# DDS-Gen.net
KiCad netlist of a schematic drawn in EAGLE
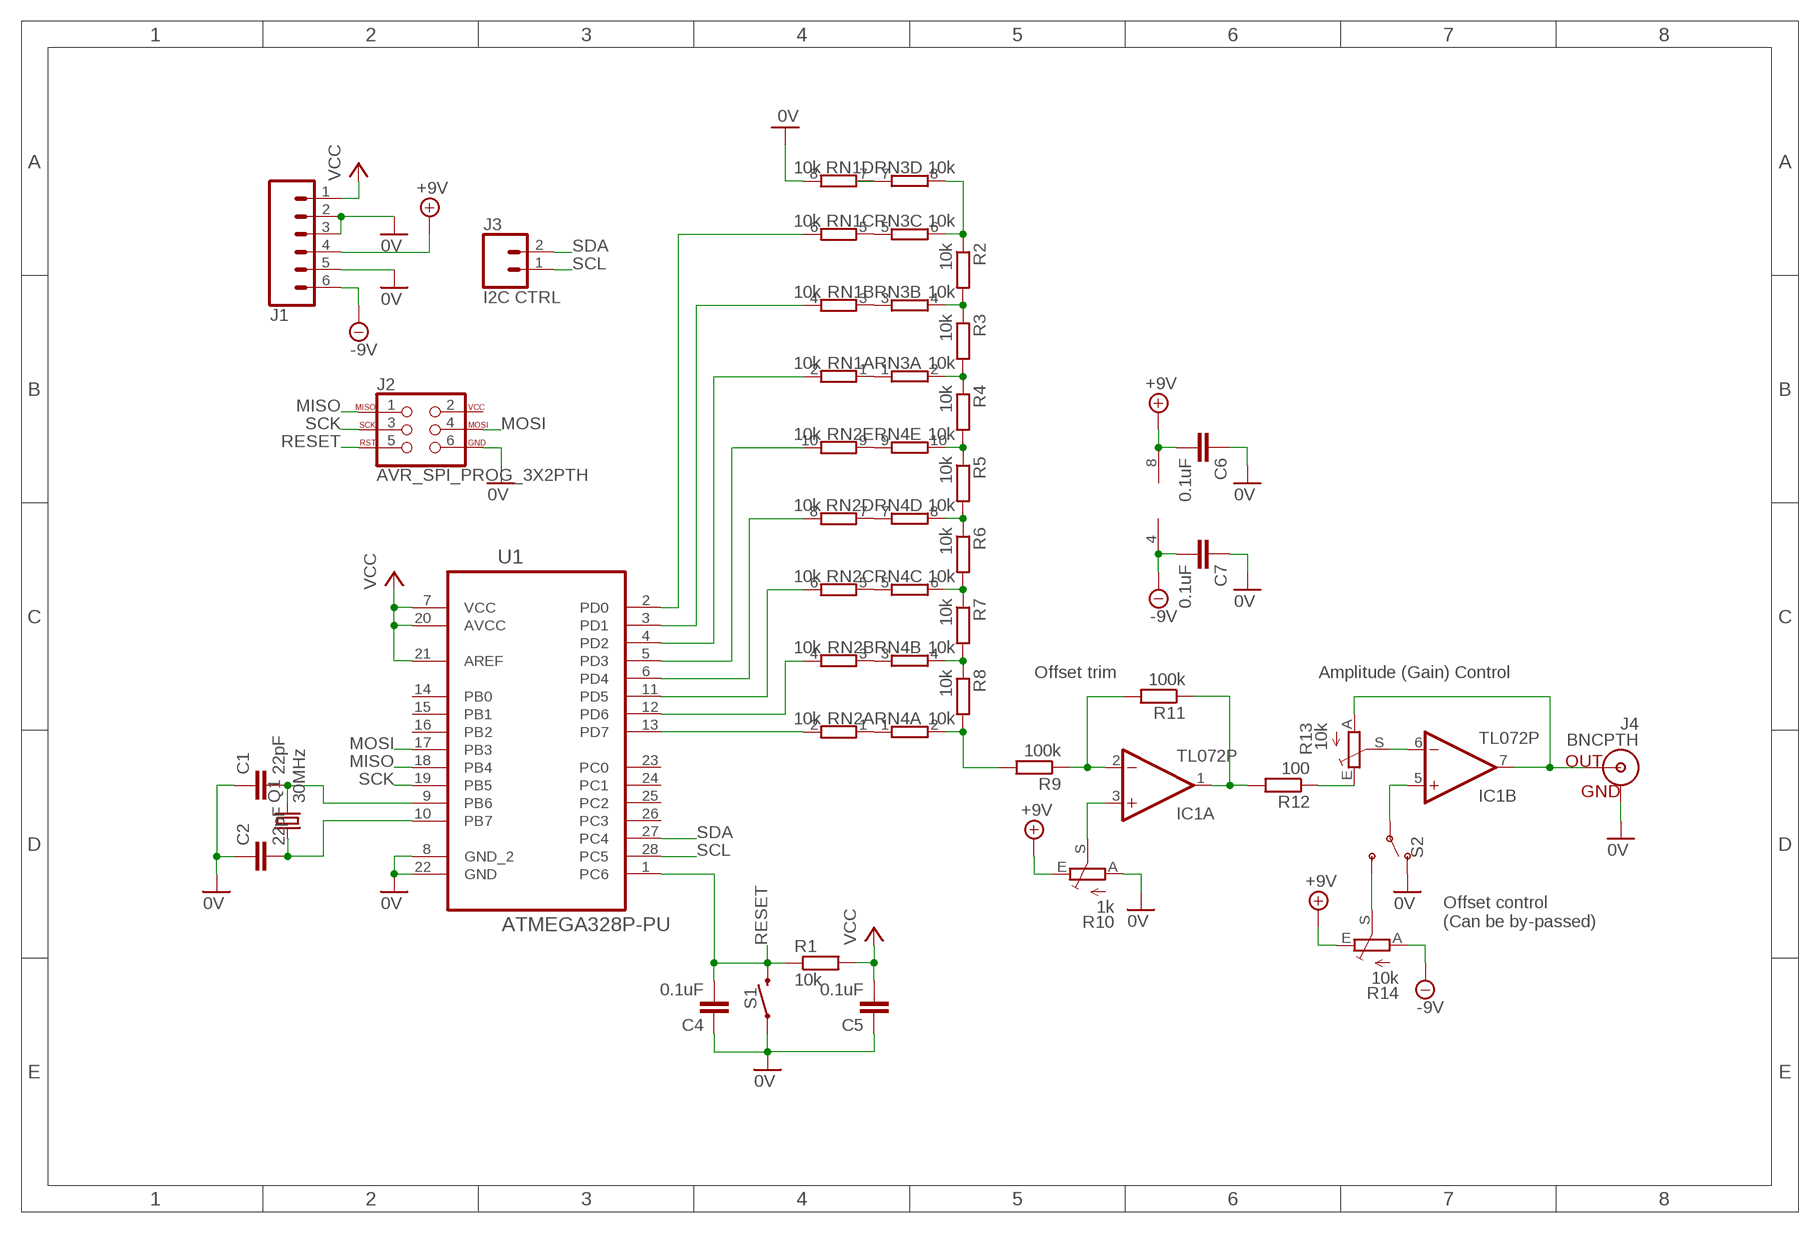
[diagram p0: schematic, sheet 1]

(export (version "E")
  (design (tool "Eeschema 10.0.6"))
  (components
    (comp (ref "C1")
      (value "22pF")
      (footprint "eagle-import:C025-025X050")
      (libsource (lib "eagle-import") (part "C-EU025-025X050"))
    )
    (comp (ref "C2")
      (value "22pF")
      (footprint "eagle-import:C025-025X050")
      (libsource (lib "eagle-import") (part "C-EU025-025X050"))
    )
    (comp (ref "C4")
      (value "0.1uF")
      (footprint "eagle-import:C025-025X050")
      (libsource (lib "eagle-import") (part "C-EU025-025X050"))
    )
    (comp (ref "C5")
      (value "0.1uF")
      (footprint "eagle-import:C025-025X050")
      (libsource (lib "eagle-import") (part "C-EU025-025X050"))
    )
    (comp (ref "C6")
      (value "0.1uF")
      (footprint "eagle-import:C025-025X050")
      (libsource (lib "eagle-import") (part "C-EU025-025X050"))
    )
    (comp (ref "C7")
      (value "0.1uF")
      (footprint "eagle-import:C025-025X050")
      (libsource (lib "eagle-import") (part "C-EU025-025X050"))
    )
    (comp (ref "IC1")
      (value "TL072P")
      (footprint "eagle-import:DIL08")
      (libsource (lib "eagle-import") (part "TL072P"))
    )
    (comp (ref "J1")
      (value "CONN_06POLAR")
      (footprint "eagle-import:MOLEX-1X6")
      (libsource (lib "eagle-import") (part "CONN_06POLAR"))
    )
    (comp (ref "J2")
      (value "AVR_SPI_PROG_3X2PTH")
      (footprint "eagle-import:2X3")
      (libsource (lib "eagle-import") (part "AVR_SPI_PROG_3X2PTH"))
    )
    (comp (ref "J3")
      (value "I2C CTRL")
      (footprint "eagle-import:MOLEX-1X2")
      (libsource (lib "eagle-import") (part "CONN_02POLAR"))
    )
    (comp (ref "J4")
      (value "BNCPTH")
      (footprint "eagle-import:BNC")
      (libsource (lib "eagle-import") (part "BNCPTH"))
    )
    (comp (ref "Q1")
      (value "30MHz")
      (footprint "eagle-import:HC49_S")
      (libsource (lib "eagle-import") (part "CRYSTALHC49S"))
    )
    (comp (ref "R1")
      (value "10k")
      (footprint "eagle-import:0204_5")
      (libsource (lib "eagle-import") (part "R-EU_0204/5"))
    )
    (comp (ref "R2")
      (value "10k")
      (footprint "eagle-import:0204_5")
      (libsource (lib "eagle-import") (part "R-EU_0204/5"))
    )
    (comp (ref "R3")
      (value "10k")
      (footprint "eagle-import:0204_5")
      (libsource (lib "eagle-import") (part "R-EU_0204/5"))
    )
    (comp (ref "R4")
      (value "10k")
      (footprint "eagle-import:0204_5")
      (libsource (lib "eagle-import") (part "R-EU_0204/5"))
    )
    (comp (ref "R5")
      (value "10k")
      (footprint "eagle-import:0204_5")
      (libsource (lib "eagle-import") (part "R-EU_0204/5"))
    )
    (comp (ref "R6")
      (value "10k")
      (footprint "eagle-import:0204_5")
      (libsource (lib "eagle-import") (part "R-EU_0204/5"))
    )
    (comp (ref "R7")
      (value "10k")
      (footprint "eagle-import:0204_5")
      (libsource (lib "eagle-import") (part "R-EU_0204/5"))
    )
    (comp (ref "R8")
      (value "10k")
      (footprint "eagle-import:0204_5")
      (libsource (lib "eagle-import") (part "R-EU_0204/5"))
    )
    (comp (ref "R9")
      (value "100k")
      (footprint "eagle-import:0204_5")
      (libsource (lib "eagle-import") (part "R-EU_0204/5"))
    )
    (comp (ref "R10")
      (value "1k")
      (footprint "eagle-import:S64W")
      (libsource (lib "eagle-import") (part "TRIM_EU-S64W"))
    )
    (comp (ref "R11")
      (value "100k")
      (footprint "eagle-import:0204V")
      (libsource (lib "eagle-import") (part "R-EU_0204/2V"))
    )
    (comp (ref "R12")
      (value "100")
      (footprint "eagle-import:0207_12")
      (libsource (lib "eagle-import") (part "R-EU_0207/12"))
    )
    (comp (ref "R13")
      (value "10k")
      (footprint "eagle-import:CIP20C-6MM")
      (libsource (lib "eagle-import") (part "TRIM_EU-CIP20C-6MM"))
    )
    (comp (ref "R14")
      (value "10k")
      (footprint "eagle-import:CIP20C-6MM")
      (libsource (lib "eagle-import") (part "TRIM_EU-CIP20C-6MM"))
    )
    (comp (ref "RN1")
      (value "10k")
      (footprint "eagle-import:SIL10")
      (libsource (lib "eagle-import") (part "E5R"))
    )
    (comp (ref "RN2")
      (value "10k")
      (footprint "eagle-import:SIL10")
      (libsource (lib "eagle-import") (part "E5R"))
    )
    (comp (ref "RN3")
      (value "10k")
      (footprint "eagle-import:SIL10")
      (libsource (lib "eagle-import") (part "E5R"))
    )
    (comp (ref "RN4")
      (value "10k")
      (footprint "eagle-import:SIL10")
      (libsource (lib "eagle-import") (part "E5R"))
    )
    (comp (ref "S1")
      (value "MOMENTARY-SWITCH-SPST-PTH-6.0MM")
      (footprint "eagle-import:TACTILE_SWITCH_PTH_6.0MM")
      (libsource (lib "eagle-import") (part "MOMENTARY-SWITCH-SPST-PTH-6.0MM"))
    )
    (comp (ref "S2")
      (value "SWITCH-SPDT-PTH-11.6X4.0MM")
      (footprint "eagle-import:SWITCH_SPDT_PTH_11.6X4.0MM")
      (libsource (lib "eagle-import") (part "SWITCH-SPDT-PTH-11.6X4.0MM"))
    )
    (comp (ref "U1")
      (value "ATMEGA328P-PU")
      (footprint "eagle-import:DIP254P762X457-28")
      (libsource (lib "eagle-import") (part "ATMEGA328P-PU"))
    )
  )
  (nets
    (net (code "1") (name "+9V") (class "Default")
      (node (ref "C6") (pin "2") (pinfunction "2_2") (pintype "passive"))
      (node (ref "IC1") (pin "8") (pinfunction "V+_8") (pintype "power_in"))
      (node (ref "J1") (pin "4") (pinfunction "4_4") (pintype "passive"))
      (node (ref "R10") (pin "E") (pinfunction "E_E") (pintype "passive"))
      (node (ref "R14") (pin "E") (pinfunction "E_E") (pintype "passive"))
    )
    (net (code "2") (name "-9V") (class "Default")
      (node (ref "C7") (pin "2") (pinfunction "2_2") (pintype "passive"))
      (node (ref "IC1") (pin "4") (pinfunction "V-_4") (pintype "power_in"))
      (node (ref "J1") (pin "6") (pinfunction "6_6") (pintype "passive"))
      (node (ref "R14") (pin "A") (pinfunction "A_A") (pintype "passive"))
    )
    (net (code "3") (name "/MISO") (class "Default")
      (node (ref "J2") (pin "1") (pinfunction "1_1") (pintype "passive"))
      (node (ref "U1") (pin "18") (pinfunction "PB4_18") (pintype "bidirectional"))
    )
    (net (code "4") (name "/MOSI") (class "Default")
      (node (ref "J2") (pin "4") (pinfunction "4_4") (pintype "passive"))
      (node (ref "U1") (pin "17") (pinfunction "PB3_17") (pintype "bidirectional"))
    )
    (net (code "5") (name "/RESET") (class "Default")
      (node (ref "C4") (pin "2") (pinfunction "2_2") (pintype "passive"))
      (node (ref "J2") (pin "5") (pinfunction "5_5") (pintype "passive"))
      (node (ref "R1") (pin "1") (pinfunction "1_1") (pintype "passive"))
      (node (ref "S1") (pin "3") (pinfunction "2_3") (pintype "passive"))
      (node (ref "U1") (pin "1") (pinfunction "PC6_1") (pintype "bidirectional"))
    )
    (net (code "6") (name "/SCK") (class "Default")
      (node (ref "J2") (pin "3") (pinfunction "3_3") (pintype "passive"))
      (node (ref "U1") (pin "19") (pinfunction "PB5_19") (pintype "bidirectional"))
    )
    (net (code "7") (name "/SCL") (class "Default")
      (node (ref "J3") (pin "1") (pinfunction "1_1") (pintype "passive"))
      (node (ref "U1") (pin "28") (pinfunction "PC5_28") (pintype "bidirectional"))
    )
    (net (code "8") (name "/SDA") (class "Default")
      (node (ref "J3") (pin "2") (pinfunction "2_2") (pintype "passive"))
      (node (ref "U1") (pin "27") (pinfunction "PC4_27") (pintype "bidirectional"))
    )
    (net (code "9") (name "0V") (class "Default")
      (node (ref "C1") (pin "1") (pinfunction "1_1") (pintype "passive"))
      (node (ref "C2") (pin "1") (pinfunction "1_1") (pintype "passive"))
      (node (ref "C4") (pin "1") (pinfunction "1_1") (pintype "passive"))
      (node (ref "C5") (pin "1") (pinfunction "1_1") (pintype "passive"))
      (node (ref "C6") (pin "1") (pinfunction "1_1") (pintype "passive"))
      (node (ref "C7") (pin "1") (pinfunction "1_1") (pintype "passive"))
      (node (ref "J1") (pin "2") (pinfunction "2_2") (pintype "passive"))
      (node (ref "J1") (pin "3") (pinfunction "3_3") (pintype "passive"))
      (node (ref "J1") (pin "5") (pinfunction "5_5") (pintype "passive"))
      (node (ref "J2") (pin "6") (pinfunction "6_6") (pintype "passive"))
      (node (ref "J4") (pin "GND") (pinfunction "GND_GND") (pintype "bidirectional"))
      (node (ref "R10") (pin "A") (pinfunction "A_A") (pintype "passive"))
      (node (ref "RN1") (pin "8") (pinfunction "2_8") (pintype "passive"))
      (node (ref "S1") (pin "1") (pinfunction "1_1") (pintype "passive"))
      (node (ref "S2") (pin "1") (pinfunction "O_1") (pintype "passive"))
      (node (ref "U1") (pin "22") (pinfunction "GND_22") (pintype "passive"))
      (node (ref "U1") (pin "8") (pinfunction "GND_2_8") (pintype "passive"))
    )
    (net (code "10") (name "Net-(IC1A-+IN)") (class "Default")
      (node (ref "IC1") (pin "3") (pinfunction "+IN_3") (pintype "input"))
      (node (ref "R10") (pin "S") (pinfunction "S_S") (pintype "passive"))
    )
    (net (code "11") (name "Net-(IC1A--IN)") (class "Default")
      (node (ref "IC1") (pin "2") (pinfunction "-IN_2") (pintype "input"))
      (node (ref "R11") (pin "2") (pinfunction "2_2") (pintype "passive"))
      (node (ref "R9") (pin "1") (pinfunction "1_1") (pintype "passive"))
    )
    (net (code "12") (name "Net-(IC1A-OUT)") (class "Default")
      (node (ref "IC1") (pin "1") (pinfunction "OUT_1") (pintype "output"))
      (node (ref "R11") (pin "1") (pinfunction "1_1") (pintype "passive"))
      (node (ref "R12") (pin "2") (pinfunction "2_2") (pintype "passive"))
    )
    (net (code "13") (name "Net-(IC1B-+IN)") (class "Default")
      (node (ref "IC1") (pin "5") (pinfunction "+IN_5") (pintype "input"))
      (node (ref "S2") (pin "2") (pinfunction "P_2") (pintype "passive"))
    )
    (net (code "14") (name "Net-(IC1B--IN)") (class "Default")
      (node (ref "IC1") (pin "6") (pinfunction "-IN_6") (pintype "input"))
      (node (ref "R13") (pin "S") (pinfunction "S_S") (pintype "passive"))
    )
    (net (code "15") (name "Net-(IC1B-OUT)") (class "Default")
      (node (ref "IC1") (pin "7") (pinfunction "OUT_7") (pintype "output"))
      (node (ref "J4") (pin "S") (pinfunction "OUT_S") (pintype "bidirectional"))
      (node (ref "R13") (pin "A") (pinfunction "A_A") (pintype "passive"))
    )
    (net (code "16") (name "Net-(R3-Pad2)") (class "Default")
      (node (ref "R3") (pin "2") (pinfunction "2_2") (pintype "passive"))
      (node (ref "R4") (pin "1") (pinfunction "1_1") (pintype "passive"))
      (node (ref "RN3") (pin "2") (pinfunction "2_2") (pintype "passive"))
    )
    (net (code "17") (name "Net-(R8-Pad2)") (class "Default")
      (node (ref "R8") (pin "2") (pinfunction "2_2") (pintype "passive"))
      (node (ref "R9") (pin "2") (pinfunction "2_2") (pintype "passive"))
      (node (ref "RN4") (pin "2") (pinfunction "2_2") (pintype "passive"))
    )
    (net (code "18") (name "Net-(R12-Pad1)") (class "Default")
      (node (ref "R12") (pin "1") (pinfunction "1_1") (pintype "passive"))
      (node (ref "R13") (pin "E") (pinfunction "E_E") (pintype "passive"))
    )
    (net (code "19") (name "Net-(RN1-Pad1)") (class "Default")
      (node (ref "RN1") (pin "1") (pinfunction "1_1") (pintype "passive"))
      (node (ref "RN3") (pin "1") (pinfunction "1_1") (pintype "passive"))
    )
    (net (code "20") (name "Net-(RN1B-1)") (class "Default")
      (node (ref "RN1") (pin "3") (pinfunction "1_3") (pintype "passive"))
      (node (ref "RN3") (pin "3") (pinfunction "1_3") (pintype "passive"))
    )
    (net (code "21") (name "Net-(RN1B-2)") (class "Default")
      (node (ref "RN1") (pin "4") (pinfunction "2_4") (pintype "passive"))
      (node (ref "U1") (pin "3") (pinfunction "PD1_3") (pintype "bidirectional"))
    )
    (net (code "22") (name "Net-(RN1C-1)") (class "Default")
      (node (ref "RN1") (pin "5") (pinfunction "1_5") (pintype "passive"))
      (node (ref "RN3") (pin "5") (pinfunction "1_5") (pintype "passive"))
    )
    (net (code "23") (name "Net-(RN1C-2)") (class "Default")
      (node (ref "RN1") (pin "6") (pinfunction "2_6") (pintype "passive"))
      (node (ref "U1") (pin "2") (pinfunction "PD0_2") (pintype "bidirectional"))
    )
    (net (code "24") (name "Net-(RN1D-1)") (class "Default")
      (node (ref "RN1") (pin "7") (pinfunction "1_7") (pintype "passive"))
      (node (ref "RN3") (pin "7") (pinfunction "1_7") (pintype "passive"))
    )
    (net (code "25") (name "Net-(RN2-Pad1)") (class "Default")
      (node (ref "RN2") (pin "1") (pinfunction "1_1") (pintype "passive"))
      (node (ref "RN4") (pin "1") (pinfunction "1_1") (pintype "passive"))
    )
    (net (code "26") (name "Net-(RN2B-1)") (class "Default")
      (node (ref "RN2") (pin "3") (pinfunction "1_3") (pintype "passive"))
      (node (ref "RN4") (pin "3") (pinfunction "1_3") (pintype "passive"))
    )
    (net (code "27") (name "Net-(RN2B-2)") (class "Default")
      (node (ref "RN2") (pin "4") (pinfunction "2_4") (pintype "passive"))
      (node (ref "U1") (pin "12") (pinfunction "PD6_12") (pintype "bidirectional"))
    )
    (net (code "28") (name "Net-(RN2C-1)") (class "Default")
      (node (ref "RN2") (pin "5") (pinfunction "1_5") (pintype "passive"))
      (node (ref "RN4") (pin "5") (pinfunction "1_5") (pintype "passive"))
    )
    (net (code "29") (name "Net-(RN2C-2)") (class "Default")
      (node (ref "RN2") (pin "6") (pinfunction "2_6") (pintype "passive"))
      (node (ref "U1") (pin "11") (pinfunction "PD5_11") (pintype "bidirectional"))
    )
    (net (code "30") (name "Net-(RN2D-1)") (class "Default")
      (node (ref "RN2") (pin "7") (pinfunction "1_7") (pintype "passive"))
      (node (ref "RN4") (pin "7") (pinfunction "1_7") (pintype "passive"))
    )
    (net (code "31") (name "Net-(RN2D-2)") (class "Default")
      (node (ref "RN2") (pin "8") (pinfunction "2_8") (pintype "passive"))
      (node (ref "U1") (pin "6") (pinfunction "PD4_6") (pintype "bidirectional"))
    )
    (net (code "32") (name "Net-(RN2E-1)") (class "Default")
      (node (ref "RN2") (pin "9") (pinfunction "1_9") (pintype "passive"))
      (node (ref "RN4") (pin "9") (pinfunction "1_9") (pintype "passive"))
    )
    (net (code "33") (name "Net-(RN2E-2)") (class "Default")
      (node (ref "RN2") (pin "10") (pinfunction "2_10") (pintype "passive"))
      (node (ref "U1") (pin "5") (pinfunction "PD3_5") (pintype "bidirectional"))
    )
    (net (code "34") (name "Net-(RN3B-2)") (class "Default")
      (node (ref "R2") (pin "2") (pinfunction "2_2") (pintype "passive"))
      (node (ref "R3") (pin "1") (pinfunction "1_1") (pintype "passive"))
      (node (ref "RN3") (pin "4") (pinfunction "2_4") (pintype "passive"))
    )
    (net (code "35") (name "Net-(RN3C-2)") (class "Default")
      (node (ref "R2") (pin "1") (pinfunction "1_1") (pintype "passive"))
      (node (ref "RN3") (pin "6") (pinfunction "2_6") (pintype "passive"))
      (node (ref "RN3") (pin "8") (pinfunction "2_8") (pintype "passive"))
    )
    (net (code "36") (name "Net-(RN4B-2)") (class "Default")
      (node (ref "R7") (pin "2") (pinfunction "2_2") (pintype "passive"))
      (node (ref "R8") (pin "1") (pinfunction "1_1") (pintype "passive"))
      (node (ref "RN4") (pin "4") (pinfunction "2_4") (pintype "passive"))
    )
    (net (code "37") (name "Net-(RN4C-2)") (class "Default")
      (node (ref "R6") (pin "2") (pinfunction "2_2") (pintype "passive"))
      (node (ref "R7") (pin "1") (pinfunction "1_1") (pintype "passive"))
      (node (ref "RN4") (pin "6") (pinfunction "2_6") (pintype "passive"))
    )
    (net (code "38") (name "Net-(RN4D-2)") (class "Default")
      (node (ref "R5") (pin "2") (pinfunction "2_2") (pintype "passive"))
      (node (ref "R6") (pin "1") (pinfunction "1_1") (pintype "passive"))
      (node (ref "RN4") (pin "8") (pinfunction "2_8") (pintype "passive"))
    )
    (net (code "39") (name "Net-(RN4E-2)") (class "Default")
      (node (ref "R4") (pin "2") (pinfunction "2_2") (pintype "passive"))
      (node (ref "R5") (pin "1") (pinfunction "1_1") (pintype "passive"))
      (node (ref "RN4") (pin "10") (pinfunction "2_10") (pintype "passive"))
    )
    (net (code "40") (name "Net-(S2-S)") (class "Default")
      (node (ref "R14") (pin "S") (pinfunction "S_S") (pintype "passive"))
      (node (ref "S2") (pin "3") (pinfunction "S_3") (pintype "passive"))
    )
    (net (code "41") (name "Net-(U1-PB6)") (class "Default")
      (node (ref "C1") (pin "2") (pinfunction "2_2") (pintype "passive"))
      (node (ref "Q1") (pin "2") (pinfunction "2_2") (pintype "passive"))
      (node (ref "U1") (pin "9") (pinfunction "PB6_9") (pintype "bidirectional"))
    )
    (net (code "42") (name "Net-(U1-PB7)") (class "Default")
      (node (ref "C2") (pin "2") (pinfunction "2_2") (pintype "passive"))
      (node (ref "Q1") (pin "1") (pinfunction "1_1") (pintype "passive"))
      (node (ref "U1") (pin "10") (pinfunction "PB7_10") (pintype "bidirectional"))
    )
    (net (code "43") (name "Net-(U1-PD2)") (class "Default")
      (node (ref "RN1") (pin "2") (pinfunction "2_2") (pintype "passive"))
      (node (ref "U1") (pin "4") (pinfunction "PD2_4") (pintype "bidirectional"))
    )
    (net (code "44") (name "Net-(U1-PD7)") (class "Default")
      (node (ref "RN2") (pin "2") (pinfunction "2_2") (pintype "passive"))
      (node (ref "U1") (pin "13") (pinfunction "PD7_13") (pintype "bidirectional"))
    )
    (net (code "45") (name "VCC") (class "Default")
      (node (ref "C5") (pin "2") (pinfunction "2_2") (pintype "passive"))
      (node (ref "J1") (pin "1") (pinfunction "1_1") (pintype "passive"))
      (node (ref "R1") (pin "2") (pinfunction "2_2") (pintype "passive"))
      (node (ref "U1") (pin "20") (pinfunction "AVCC_20") (pintype "power_in"))
      (node (ref "U1") (pin "21") (pinfunction "AREF_21") (pintype "input"))
      (node (ref "U1") (pin "7") (pinfunction "VCC_7") (pintype "power_in"))
    )
    (net (code "46") (name "unconnected-(J2-Pad2)") (class "Default")
      (node (ref "J2") (pin "2") (pinfunction "2_2") (pintype "passive"))
    )
    (net (code "47") (name "unconnected-(U1-PB0-Pad14)") (class "Default")
      (node (ref "U1") (pin "14") (pinfunction "PB0_14") (pintype "bidirectional"))
    )
    (net (code "48") (name "unconnected-(U1-PB1-Pad15)") (class "Default")
      (node (ref "U1") (pin "15") (pinfunction "PB1_15") (pintype "bidirectional"))
    )
    (net (code "49") (name "unconnected-(U1-PB2-Pad16)") (class "Default")
      (node (ref "U1") (pin "16") (pinfunction "PB2_16") (pintype "bidirectional"))
    )
    (net (code "50") (name "unconnected-(U1-PC0-Pad23)") (class "Default")
      (node (ref "U1") (pin "23") (pinfunction "PC0_23") (pintype "bidirectional"))
    )
    (net (code "51") (name "unconnected-(U1-PC1-Pad24)") (class "Default")
      (node (ref "U1") (pin "24") (pinfunction "PC1_24") (pintype "bidirectional"))
    )
    (net (code "52") (name "unconnected-(U1-PC2-Pad25)") (class "Default")
      (node (ref "U1") (pin "25") (pinfunction "PC2_25") (pintype "bidirectional"))
    )
    (net (code "53") (name "unconnected-(U1-PC3-Pad26)") (class "Default")
      (node (ref "U1") (pin "26") (pinfunction "PC3_26") (pintype "bidirectional"))
    )
  )
)
